# Grove_-_12-bit_Magnetic_Rotary_Position_.net
KiCad netlist of a schematic drawn in EAGLE
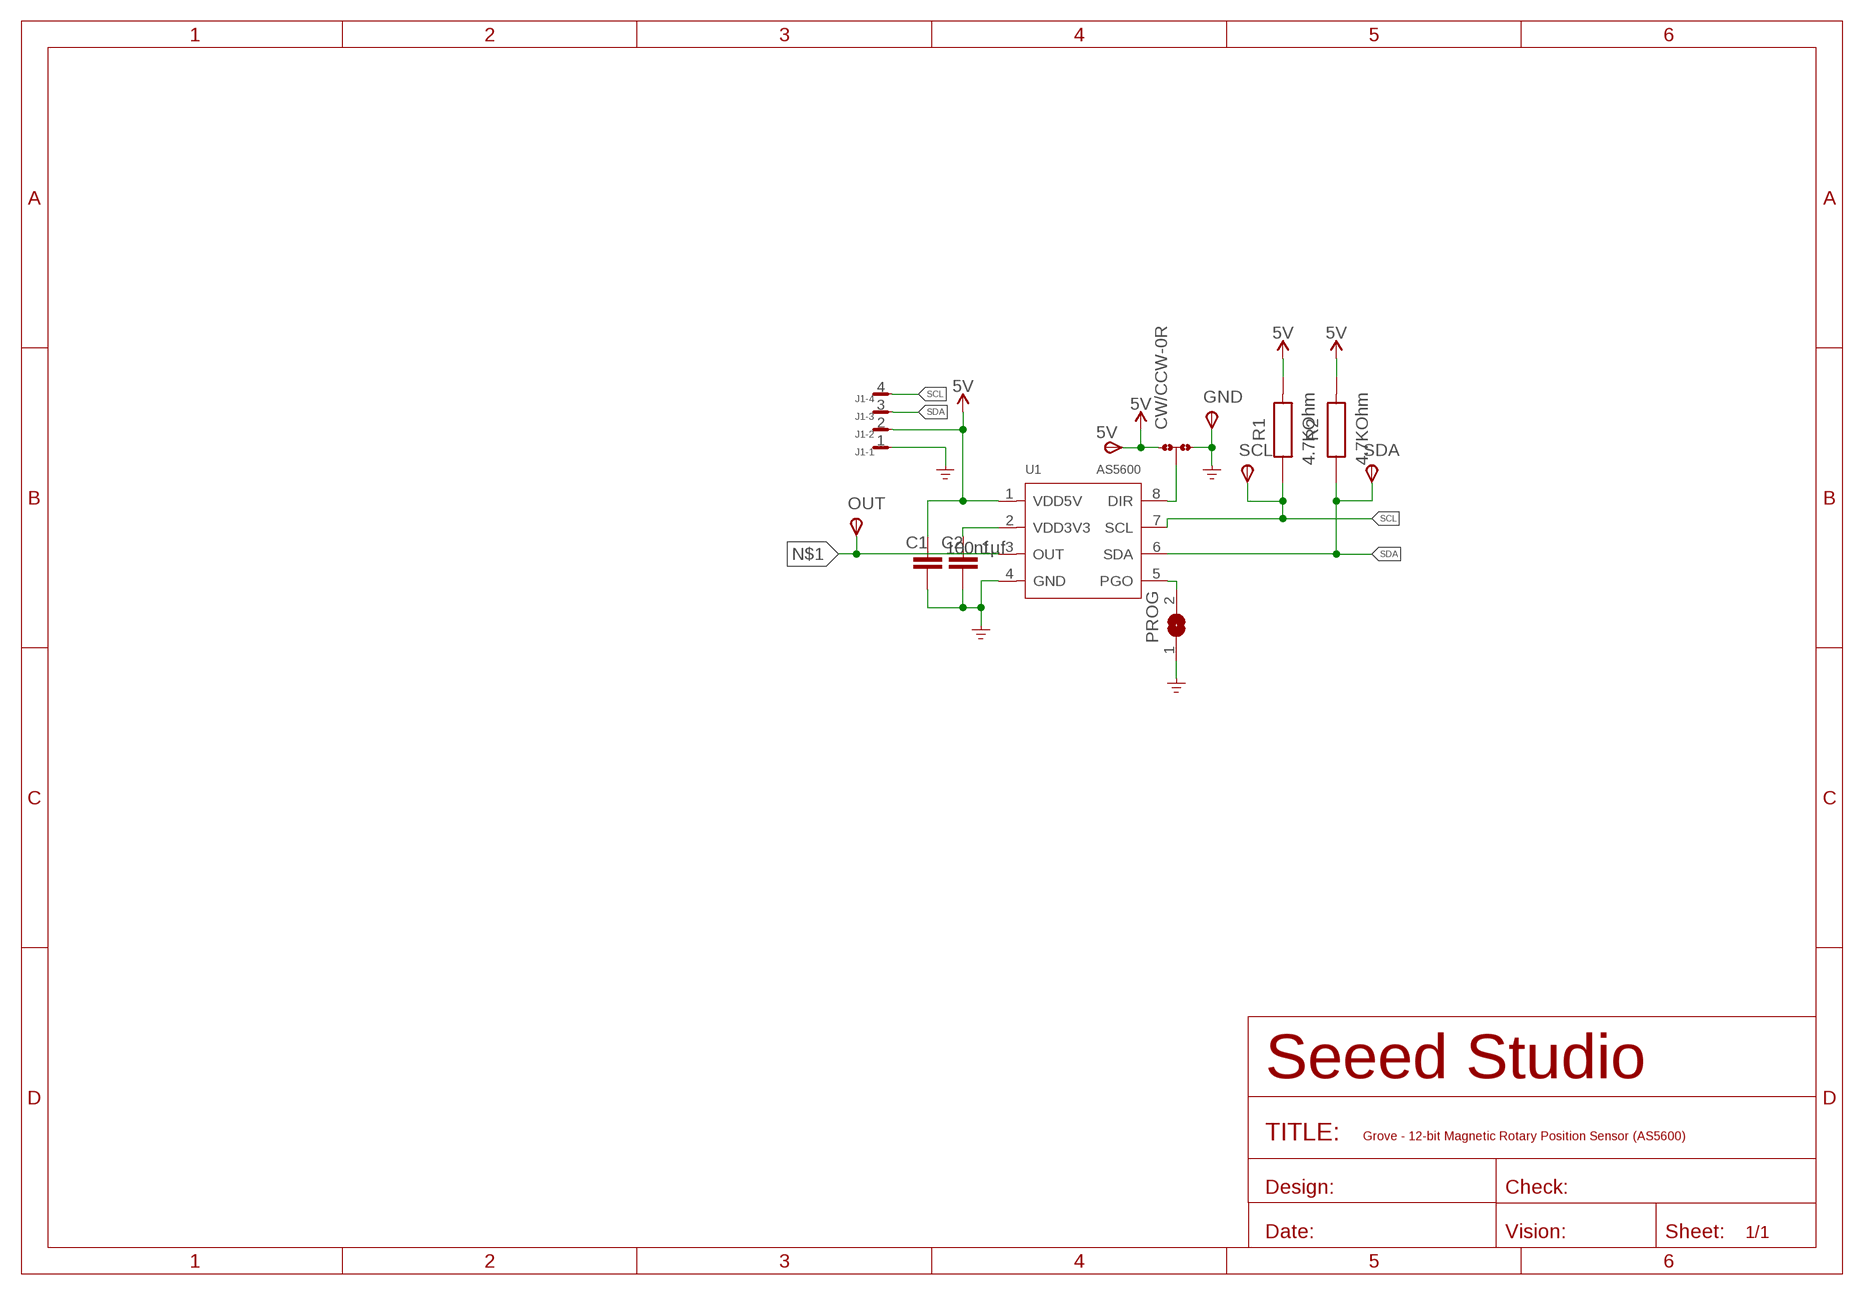
[diagram p0: schematic, sheet 1]

(export (version "E")
  (design (tool "Eeschema 10.0.6"))
  (components
    (comp (ref "5V")
      (value "TPSB2,54")
      (footprint "eagle-import:B2,54")
      (libsource (lib "eagle-import") (part "TPSB2,54"))
    )
    (comp (ref "C1")
      (value "100nf")
      (footprint "eagle-import:CAPC2012X110")
      (libsource (lib "eagle-import") (part "CCHIP-0805(2012-METRIC)_"))
    )
    (comp (ref "C2")
      (value "1µf")
      (footprint "eagle-import:CAPC2012X110")
      (libsource (lib "eagle-import") (part "CCHIP-0805(2012-METRIC)_"))
    )
    (comp (ref "CW/CCW")
      (value "0R-JUMPA")
      (footprint "eagle-import:A0R-JMP")
      (libsource (lib "eagle-import") (part "0R-JUMPA"))
    )
    (comp (ref "GND")
      (value "TPSB2,54")
      (footprint "eagle-import:B2,54")
      (libsource (lib "eagle-import") (part "TPSB2,54"))
    )
    (comp (ref "J1")
      (value "SM04B-SRSS-TB")
      (footprint "eagle-import:SM04B-SRSS-TB")
      (libsource (lib "eagle-import") (part "SM04B-SRSS-TB"))
    )
    (comp (ref "OUT")
      (value "TPSB2,54")
      (footprint "eagle-import:B2,54")
      (libsource (lib "eagle-import") (part "TPSB2,54"))
    )
    (comp (ref "PROG")
      (value "SJ")
      (footprint "eagle-import:SJ")
      (libsource (lib "eagle-import") (part "SJ"))
    )
    (comp (ref "R1")
      (value "4.7KOhm")
      (footprint "eagle-import:WRIS-KSKE_0805_2.0X1.25X0.6(LXWXH)")
      (libsource (lib "eagle-import") (part "WRIS-KSKE_0805_2.0X1.25X0.6_560050320001"))
    )
    (comp (ref "R2")
      (value "4.7KOhm")
      (footprint "eagle-import:WRIS-KSKE_0805_2.0X1.25X0.6(LXWXH)")
      (libsource (lib "eagle-import") (part "WRIS-KSKE_0805_2.0X1.25X0.6_560050320001"))
    )
    (comp (ref "SCL")
      (value "TPSB2,54")
      (footprint "eagle-import:B2,54")
      (libsource (lib "eagle-import") (part "TPSB2,54"))
    )
    (comp (ref "SDA")
      (value "TPSB2,54")
      (footprint "eagle-import:B2,54")
      (libsource (lib "eagle-import") (part "TPSB2,54"))
    )
    (comp (ref "U1")
      (value "AS5600")
      (footprint "eagle-import:SOIC8-1.27-5X4MM")
      (libsource (lib "eagle-import") (part "SENSOR-AS5600"))
    )
  )
  (nets
    (net (code "1") (name "5V") (class "Default")
      (node (ref "5V") (pin "TP") (pinfunction "PP_TP") (pintype "input"))
      (node (ref "C1") (pin "1") (pinfunction "1_1") (pintype "passive"))
      (node (ref "CW/CCW") (pin "3") (pinfunction "3_3") (pintype "passive"))
      (node (ref "J1") (pin "2") (pinfunction "P_2") (pintype "bidirectional"))
      (node (ref "R1") (pin "2") (pinfunction "2_2") (pintype "passive"))
      (node (ref "R2") (pin "2") (pinfunction "2_2") (pintype "passive"))
      (node (ref "U1") (pin "1") (pinfunction "VDD5V_1") (pintype "bidirectional"))
    )
    (net (code "2") (name "GND_POWER") (class "Default")
      (node (ref "C1") (pin "2") (pinfunction "2_2") (pintype "passive"))
      (node (ref "C2") (pin "2") (pinfunction "2_2") (pintype "passive"))
      (node (ref "CW/CCW") (pin "1") (pinfunction "1_1") (pintype "passive"))
      (node (ref "GND") (pin "TP") (pinfunction "PP_TP") (pintype "input"))
      (node (ref "J1") (pin "1") (pinfunction "P_1") (pintype "bidirectional"))
      (node (ref "PROG") (pin "1") (pinfunction "1_1") (pintype "passive"))
      (node (ref "U1") (pin "4") (pinfunction "GND_4") (pintype "bidirectional"))
    )
    (net (code "3") (name "N$1") (class "Default")
      (node (ref "OUT") (pin "TP") (pinfunction "PP_TP") (pintype "input"))
      (node (ref "U1") (pin "3") (pinfunction "OUT_3") (pintype "bidirectional"))
    )
    (net (code "4") (name "Net-(U1-DIR)") (class "Default")
      (node (ref "CW/CCW") (pin "2") (pinfunction "2_2") (pintype "passive"))
      (node (ref "U1") (pin "8") (pinfunction "DIR_8") (pintype "bidirectional"))
    )
    (net (code "5") (name "Net-(U1-PGO)") (class "Default")
      (node (ref "PROG") (pin "2") (pinfunction "2_2") (pintype "passive"))
      (node (ref "U1") (pin "5") (pinfunction "PGO_5") (pintype "bidirectional"))
    )
    (net (code "6") (name "Net-(U1-VDD3V3)") (class "Default")
      (node (ref "C2") (pin "1") (pinfunction "1_1") (pintype "passive"))
      (node (ref "U1") (pin "2") (pinfunction "VDD3V3_2") (pintype "bidirectional"))
    )
    (net (code "7") (name "SCL") (class "Default")
      (node (ref "J1") (pin "4") (pinfunction "P_4") (pintype "bidirectional"))
      (node (ref "R1") (pin "1") (pinfunction "1_1") (pintype "passive"))
      (node (ref "SCL") (pin "TP") (pinfunction "PP_TP") (pintype "input"))
      (node (ref "U1") (pin "7") (pinfunction "SCL_7") (pintype "bidirectional"))
    )
    (net (code "8") (name "SDA") (class "Default")
      (node (ref "J1") (pin "3") (pinfunction "P_3") (pintype "bidirectional"))
      (node (ref "R2") (pin "1") (pinfunction "1_1") (pintype "passive"))
      (node (ref "SDA") (pin "TP") (pinfunction "PP_TP") (pintype "input"))
      (node (ref "U1") (pin "6") (pinfunction "SDA_6") (pintype "bidirectional"))
    )
  )
)
